# GD32F207RG.net
KiCad netlist of a schematic drawn in EAGLE
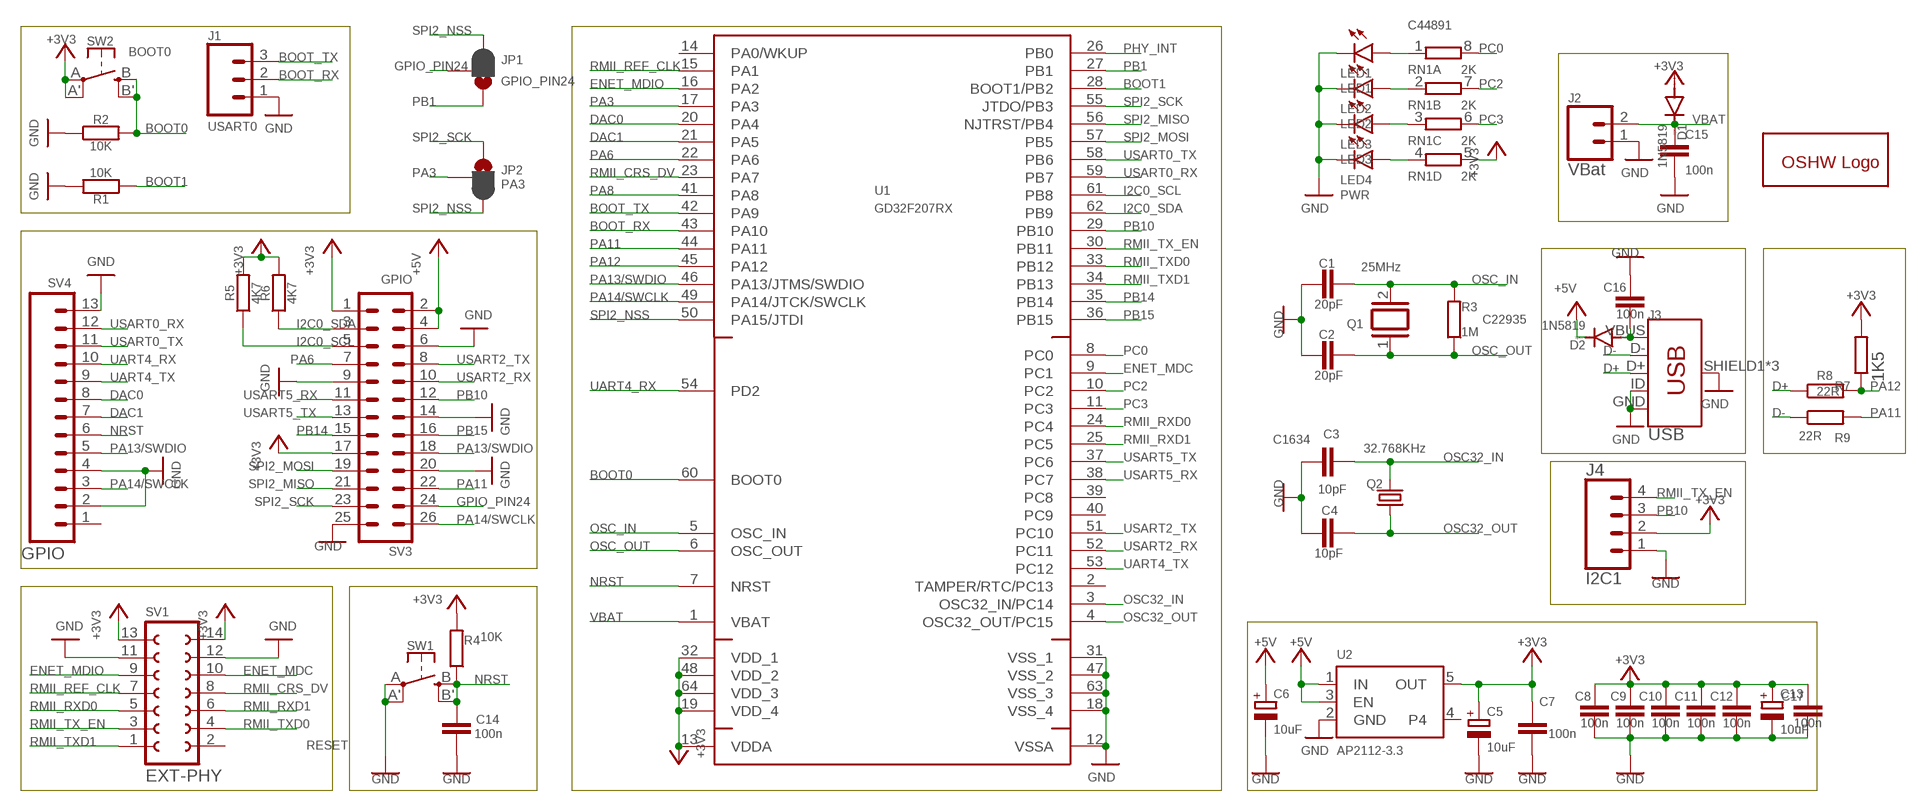
[diagram p0: schematic, sheet 1]

(export (version "E")
  (design (tool "Eeschema 10.0.6"))
  (components
    (comp (ref "C1")
      (value "20pF")
      (footprint "eagle-import:C0603")
      (libsource (lib "eagle-import") (part "C-EUC0603"))
    )
    (comp (ref "C2")
      (value "20pF")
      (footprint "eagle-import:C0603")
      (libsource (lib "eagle-import") (part "C-EUC0603"))
    )
    (comp (ref "C3")
      (value "10pF")
      (footprint "eagle-import:C0603")
      (fields (field (name "JLCPCB") "C1634"))
      (libsource (lib "eagle-import") (part "C-EUC0603"))
    )
    (comp (ref "C4")
      (value "10pF")
      (footprint "eagle-import:C0603")
      (libsource (lib "eagle-import") (part "C-EUC0603"))
    )
    (comp (ref "C5")
      (value "10uF")
      (footprint "eagle-import:A_3216-18R")
      (libsource (lib "eagle-import") (part "CPOL-EUA/3216-18R"))
    )
    (comp (ref "C6")
      (value "10uF")
      (footprint "eagle-import:A_3216-18R")
      (libsource (lib "eagle-import") (part "CPOL-EUA/3216-18R"))
    )
    (comp (ref "C7")
      (value "100n")
      (footprint "eagle-import:C0603")
      (libsource (lib "eagle-import") (part "C-EUC0603"))
    )
    (comp (ref "C8")
      (value "100n")
      (footprint "eagle-import:C0603")
      (libsource (lib "eagle-import") (part "C-EUC0603"))
    )
    (comp (ref "C9")
      (value "100n")
      (footprint "eagle-import:C0603")
      (libsource (lib "eagle-import") (part "C-EUC0603"))
    )
    (comp (ref "C10")
      (value "100n")
      (footprint "eagle-import:C0603")
      (libsource (lib "eagle-import") (part "C-EUC0603"))
    )
    (comp (ref "C11")
      (value "100n")
      (footprint "eagle-import:C0603")
      (libsource (lib "eagle-import") (part "C-EUC0603"))
    )
    (comp (ref "C12")
      (value "100n")
      (footprint "eagle-import:C0603")
      (libsource (lib "eagle-import") (part "C-EUC0603"))
    )
    (comp (ref "C13")
      (value "10uF")
      (footprint "eagle-import:A_3216-18R")
      (libsource (lib "eagle-import") (part "CPOL-EUA/3216-18R"))
    )
    (comp (ref "C14")
      (value "100n")
      (footprint "eagle-import:C0603")
      (libsource (lib "eagle-import") (part "C-EUC0603"))
    )
    (comp (ref "C15")
      (value "100n")
      (footprint "eagle-import:C0603")
      (libsource (lib "eagle-import") (part "C-EUC0603"))
    )
    (comp (ref "C16")
      (value "100n")
      (footprint "eagle-import:C0603")
      (libsource (lib "eagle-import") (part "C-EUC0603"))
    )
    (comp (ref "C17")
      (value "100n")
      (footprint "eagle-import:C0603")
      (libsource (lib "eagle-import") (part "C-EUC0603"))
    )
    (comp (ref "D1")
      (value "1N5819")
      (footprint "eagle-import:SOD323-R")
      (libsource (lib "eagle-import") (part "DIODE-SOD323-R"))
    )
    (comp (ref "D2")
      (value "1N5819")
      (footprint "eagle-import:SOD323-R")
      (libsource (lib "eagle-import") (part "DIODE-SOD323-R"))
    )
    (comp (ref "GOLD_ORB_SM1")
      (value "OSHWLOGOLOGO5MM")
      (footprint "eagle-import:OSHW_5MM")
      (libsource (lib "eagle-import") (part "OSHWLOGOLOGO5MM"))
    )
    (comp (ref "J1")
      (value "USART0")
      (footprint "eagle-import:1X03")
      (libsource (lib "eagle-import") (part "CONN_03"))
    )
    (comp (ref "J2")
      (value "VBat")
      (footprint "eagle-import:JST-2-PTH")
      (libsource (lib "eagle-import") (part "CONN_02JST-PTH-2"))
    )
    (comp (ref "J3")
      (value "USB")
      (footprint "eagle-import:USB-B-MICRO-SMD")
      (libsource (lib "eagle-import") (part "USB_MICRO-B_FEMALE-SMT"))
    )
    (comp (ref "J4")
      (value "I2C1")
      (footprint "eagle-import:1X04")
      (libsource (lib "eagle-import") (part "CONN_04"))
    )
    (comp (ref "JP1")
      (value "GPIO_PIN24")
      (footprint "eagle-import:SMT-JUMPER_3_1-NC_PASTE_SILK")
      (libsource (lib "eagle-import") (part "JUMPER-SMT_3_1-NC_PASTE_SILK"))
    )
    (comp (ref "JP2")
      (value "PA3")
      (footprint "eagle-import:SMT-JUMPER_3_1-NC_PASTE_SILK")
      (libsource (lib "eagle-import") (part "JUMPER-SMT_3_1-NC_PASTE_SILK"))
    )
    (comp (ref "LED1")
      (value "LED1")
      (footprint "eagle-import:CHIP-LED0603")
      (libsource (lib "eagle-import") (part "LEDCHIP-LED0603"))
    )
    (comp (ref "LED2")
      (value "LED2")
      (footprint "eagle-import:CHIP-LED0603")
      (libsource (lib "eagle-import") (part "LEDCHIP-LED0603"))
    )
    (comp (ref "LED3")
      (value "LED3")
      (footprint "eagle-import:CHIP-LED0603")
      (libsource (lib "eagle-import") (part "LEDCHIP-LED0603"))
    )
    (comp (ref "LED4")
      (value "PWR")
      (footprint "eagle-import:CHIP-LED0603")
      (libsource (lib "eagle-import") (part "LEDCHIP-LED0603"))
    )
    (comp (ref "Q1")
      (value "25MHz")
      (footprint "eagle-import:QS")
      (libsource (lib "eagle-import") (part "XTAL/S"))
    )
    (comp (ref "Q2")
      (value "32.768KHz")
      (footprint "eagle-import:TC26H")
      (libsource (lib "eagle-import") (part "CRYSTALTC26H"))
    )
    (comp (ref "R1")
      (value "10K")
      (footprint "eagle-import:R0603")
      (libsource (lib "eagle-import") (part "R-EU_R0603"))
    )
    (comp (ref "R2")
      (value "10K")
      (footprint "eagle-import:R0603")
      (libsource (lib "eagle-import") (part "R-EU_R0603"))
    )
    (comp (ref "R3")
      (value "1M")
      (footprint "eagle-import:R0603")
      (fields (field (name "JLCPCB") "C22935"))
      (libsource (lib "eagle-import") (part "R-EU_R0603"))
    )
    (comp (ref "R4")
      (value "10K")
      (footprint "eagle-import:R0603")
      (libsource (lib "eagle-import") (part "R-EU_R0603"))
    )
    (comp (ref "R5")
      (value "4K7")
      (footprint "eagle-import:R0603")
      (libsource (lib "eagle-import") (part "R-EU_R0603"))
    )
    (comp (ref "R6")
      (value "4K7")
      (footprint "eagle-import:R0603")
      (libsource (lib "eagle-import") (part "R-EU_R0603"))
    )
    (comp (ref "R7")
      (value "1K5")
      (footprint "eagle-import:R0603")
      (libsource (lib "eagle-import") (part "R-EU_R0603"))
    )
    (comp (ref "R8")
      (value "22R")
      (footprint "eagle-import:R0603")
      (libsource (lib "eagle-import") (part "R-EU_R0603"))
    )
    (comp (ref "R9")
      (value "22R")
      (footprint "eagle-import:R0603")
      (libsource (lib "eagle-import") (part "R-EU_R0603"))
    )
    (comp (ref "RN1")
      (value "2K")
      (footprint "eagle-import:4X0402ARV341")
      (fields (field (name "JLCPCB") "C44891"))
      (libsource (lib "eagle-import") (part "4R-N0402ARV341"))
    )
    (comp (ref "SV1")
      (value "EXT-PHY")
      (footprint "eagle-import:FE07-2W")
      (libsource (lib "eagle-import") (part "FE07-2W"))
    )
    (comp (ref "SV3")
      (value "GPIO")
      (footprint "eagle-import:MA13-2")
      (libsource (lib "eagle-import") (part "MA13-2"))
    )
    (comp (ref "SV4")
      (value "GPIO")
      (footprint "eagle-import:1X13")
      (libsource (lib "eagle-import") (part "CONN_13"))
    )
    (comp (ref "SW1")
      (value "RESET")
      (footprint "eagle-import:EVQ-Q2")
      (libsource (lib "eagle-import") (part "SPST_TACT-EVQQ2"))
    )
    (comp (ref "SW2")
      (value "BOOT0")
      (footprint "eagle-import:EVQ-Q2")
      (libsource (lib "eagle-import") (part "SPST_TACT-EVQQ2"))
    )
    (comp (ref "U1")
      (value "GD32F207RX")
      (footprint "eagle-import:LQFP64")
      (libsource (lib "eagle-import") (part "GD32F207RX"))
    )
    (comp (ref "U2")
      (value "AP2112-3.3")
      (footprint "eagle-import:SOT23-5")
      (libsource (lib "eagle-import") (part "VREG_SOT23-5"))
    )
  )
  (nets
    (net (code "1") (name "+3V3") (class "Default")
      (node (ref "C10") (pin "1") (pinfunction "1_1") (pintype "passive"))
      (node (ref "C11") (pin "1") (pinfunction "1_1") (pintype "passive"))
      (node (ref "C12") (pin "1") (pinfunction "1_1") (pintype "passive"))
      (node (ref "C13") (pin "+") (pinfunction "+_+") (pintype "passive"))
      (node (ref "C17") (pin "1") (pinfunction "1_1") (pintype "passive"))
      (node (ref "C5") (pin "+") (pinfunction "+_+") (pintype "passive"))
      (node (ref "C7") (pin "1") (pinfunction "1_1") (pintype "passive"))
      (node (ref "C8") (pin "1") (pinfunction "1_1") (pintype "passive"))
      (node (ref "C9") (pin "1") (pinfunction "1_1") (pintype "passive"))
      (node (ref "D1") (pin "A") (pinfunction "A_A") (pintype "passive"))
      (node (ref "J4") (pin "2") (pinfunction "2_2") (pintype "passive"))
      (node (ref "R4") (pin "2") (pinfunction "2_2") (pintype "passive"))
      (node (ref "R5") (pin "2") (pinfunction "2_2") (pintype "passive"))
      (node (ref "R6") (pin "2") (pinfunction "2_2") (pintype "passive"))
      (node (ref "R7") (pin "2") (pinfunction "2_2") (pintype "passive"))
      (node (ref "RN1") (pin "5") (pinfunction "2_5") (pintype "passive"))
      (node (ref "SV1") (pin "13") (pinfunction "13_13") (pintype "passive"))
      (node (ref "SV1") (pin "14") (pinfunction "14_14") (pintype "passive"))
      (node (ref "SV3") (pin "1") (pinfunction "1_1") (pintype "passive"))
      (node (ref "SV3") (pin "17") (pinfunction "17_17") (pintype "passive"))
      (node (ref "SW2") (pin "A") (pinfunction "P_A") (pintype "passive"))
      (node (ref "SW2") (pin "A'") (pinfunction "P1_A'") (pintype "passive"))
      (node (ref "U1") (pin "13") (pinfunction "VDDA_13") (pintype "power_in"))
      (node (ref "U1") (pin "19") (pinfunction "VDD_4_19") (pintype "power_in"))
      (node (ref "U1") (pin "32") (pinfunction "VDD_1_32") (pintype "power_in"))
      (node (ref "U1") (pin "48") (pinfunction "VDD_2_48") (pintype "power_in"))
      (node (ref "U1") (pin "64") (pinfunction "VDD_3_64") (pintype "power_in"))
      (node (ref "U2") (pin "5") (pinfunction "OUT_5") (pintype "power_in"))
    )
    (net (code "2") (name "+5V") (class "Default")
      (node (ref "C6") (pin "+") (pinfunction "+_+") (pintype "passive"))
      (node (ref "D2") (pin "C") (pinfunction "C_C") (pintype "passive"))
      (node (ref "SV3") (pin "2") (pinfunction "2_2") (pintype "passive"))
      (node (ref "SV3") (pin "4") (pinfunction "4_4") (pintype "passive"))
      (node (ref "U2") (pin "1") (pinfunction "IN_1") (pintype "power_in"))
      (node (ref "U2") (pin "3") (pinfunction "EN_3") (pintype "input"))
    )
    (net (code "3") (name "/BOOT0") (class "Default")
      (node (ref "R2") (pin "2") (pinfunction "2_2") (pintype "passive"))
      (node (ref "SW2") (pin "B") (pinfunction "S_B") (pintype "passive"))
      (node (ref "SW2") (pin "B'") (pinfunction "S1_B'") (pintype "passive"))
      (node (ref "U1") (pin "60") (pinfunction "BOOT0_60") (pintype "bidirectional"))
    )
    (net (code "4") (name "/BOOT1") (class "Default")
      (node (ref "R1") (pin "1") (pinfunction "1_1") (pintype "passive"))
      (node (ref "U1") (pin "28") (pinfunction "BOOT1/PB2_28") (pintype "bidirectional"))
    )
    (net (code "5") (name "/BOOT_RX") (class "Default")
      (node (ref "J1") (pin "2") (pinfunction "2_2") (pintype "passive"))
      (node (ref "U1") (pin "43") (pinfunction "PA10_43") (pintype "bidirectional"))
    )
    (net (code "6") (name "/BOOT_TX") (class "Default")
      (node (ref "J1") (pin "3") (pinfunction "3_3") (pintype "passive"))
      (node (ref "U1") (pin "42") (pinfunction "PA9_42") (pintype "bidirectional"))
    )
    (net (code "7") (name "/D+") (class "Default")
      (node (ref "J3") (pin "D+") (pinfunction "D+_D+") (pintype "bidirectional"))
      (node (ref "R8") (pin "1") (pinfunction "1_1") (pintype "passive"))
    )
    (net (code "8") (name "/D-") (class "Default")
      (node (ref "J3") (pin "D-") (pinfunction "D-_D-") (pintype "bidirectional"))
      (node (ref "R9") (pin "1") (pinfunction "1_1") (pintype "passive"))
    )
    (net (code "9") (name "/DAC0") (class "Default")
      (node (ref "SV4") (pin "8") (pinfunction "8_8") (pintype "passive"))
      (node (ref "U1") (pin "20") (pinfunction "PA4_20") (pintype "bidirectional"))
    )
    (net (code "10") (name "/DAC1") (class "Default")
      (node (ref "SV4") (pin "7") (pinfunction "7_7") (pintype "passive"))
      (node (ref "U1") (pin "21") (pinfunction "PA5_21") (pintype "bidirectional"))
    )
    (net (code "11") (name "/ENET_MDC") (class "Default")
      (node (ref "SV1") (pin "10") (pinfunction "10_10") (pintype "passive"))
      (node (ref "U1") (pin "9") (pinfunction "PC1_9") (pintype "bidirectional"))
    )
    (net (code "12") (name "/ENET_MDIO") (class "Default")
      (node (ref "SV1") (pin "9") (pinfunction "9_9") (pintype "passive"))
      (node (ref "U1") (pin "16") (pinfunction "PA2_16") (pintype "bidirectional"))
    )
    (net (code "13") (name "/GPIO_PIN24") (class "Default")
      (node (ref "JP1") (pin "2") (pinfunction "2_2") (pintype "passive"))
      (node (ref "SV3") (pin "24") (pinfunction "24_24") (pintype "passive"))
    )
    (net (code "14") (name "/I2C0_SCL") (class "Default")
      (node (ref "R5") (pin "1") (pinfunction "1_1") (pintype "passive"))
      (node (ref "SV3") (pin "5") (pinfunction "5_5") (pintype "passive"))
      (node (ref "U1") (pin "61") (pinfunction "PB8_61") (pintype "bidirectional"))
    )
    (net (code "15") (name "/I2C0_SDA") (class "Default")
      (node (ref "R6") (pin "1") (pinfunction "1_1") (pintype "passive"))
      (node (ref "SV3") (pin "3") (pinfunction "3_3") (pintype "passive"))
      (node (ref "U1") (pin "62") (pinfunction "PB9_62") (pintype "bidirectional"))
    )
    (net (code "16") (name "/NRST") (class "Default")
      (node (ref "C14") (pin "1") (pinfunction "1_1") (pintype "passive"))
      (node (ref "R4") (pin "1") (pinfunction "1_1") (pintype "passive"))
      (node (ref "SV4") (pin "6") (pinfunction "6_6") (pintype "passive"))
      (node (ref "SW1") (pin "B") (pinfunction "S_B") (pintype "passive"))
      (node (ref "SW1") (pin "B'") (pinfunction "S1_B'") (pintype "passive"))
      (node (ref "U1") (pin "7") (pinfunction "NRST_7") (pintype "power_in"))
    )
    (net (code "17") (name "/OSC32_IN") (class "Default")
      (node (ref "C3") (pin "2") (pinfunction "2_2") (pintype "passive"))
      (node (ref "Q2") (pin "2") (pinfunction "2_2") (pintype "passive"))
      (node (ref "U1") (pin "3") (pinfunction "OSC32_IN/PC14_3") (pintype "bidirectional"))
    )
    (net (code "18") (name "/OSC32_OUT") (class "Default")
      (node (ref "C4") (pin "2") (pinfunction "2_2") (pintype "passive"))
      (node (ref "Q2") (pin "1") (pinfunction "1_1") (pintype "passive"))
      (node (ref "U1") (pin "4") (pinfunction "OSC32_OUT/PC15_4") (pintype "bidirectional"))
    )
    (net (code "19") (name "/OSC_IN") (class "Default")
      (node (ref "C1") (pin "2") (pinfunction "2_2") (pintype "passive"))
      (node (ref "Q1") (pin "2") (pinfunction "2_2") (pintype "passive"))
      (node (ref "R3") (pin "2") (pinfunction "2_2") (pintype "passive"))
      (node (ref "U1") (pin "5") (pinfunction "OSC_IN_5") (pintype "bidirectional"))
    )
    (net (code "20") (name "/OSC_OUT") (class "Default")
      (node (ref "C2") (pin "2") (pinfunction "2_2") (pintype "passive"))
      (node (ref "Q1") (pin "1") (pinfunction "1_1") (pintype "passive"))
      (node (ref "R3") (pin "1") (pinfunction "1_1") (pintype "passive"))
      (node (ref "U1") (pin "6") (pinfunction "OSC_OUT_6") (pintype "bidirectional"))
    )
    (net (code "21") (name "/PA3") (class "Default")
      (node (ref "JP2") (pin "2") (pinfunction "2_2") (pintype "passive"))
      (node (ref "U1") (pin "17") (pinfunction "PA3_17") (pintype "bidirectional"))
    )
    (net (code "22") (name "/PA6") (class "Default")
      (node (ref "SV3") (pin "7") (pinfunction "7_7") (pintype "passive"))
      (node (ref "U1") (pin "22") (pinfunction "PA6_22") (pintype "bidirectional"))
    )
    (net (code "23") (name "/PA8") (class "Default")
      (node (ref "U1") (pin "41") (pinfunction "PA8_41") (pintype "bidirectional"))
    )
    (net (code "24") (name "/PA11") (class "Default")
      (node (ref "R9") (pin "2") (pinfunction "2_2") (pintype "passive"))
      (node (ref "SV3") (pin "22") (pinfunction "22_22") (pintype "passive"))
      (node (ref "U1") (pin "44") (pinfunction "PA11_44") (pintype "bidirectional"))
    )
    (net (code "25") (name "/PA12") (class "Default")
      (node (ref "R7") (pin "1") (pinfunction "1_1") (pintype "passive"))
      (node (ref "R8") (pin "2") (pinfunction "2_2") (pintype "passive"))
      (node (ref "U1") (pin "45") (pinfunction "PA12_45") (pintype "bidirectional"))
    )
    (net (code "26") (name "/PA13{slash}SWDIO") (class "Default")
      (node (ref "SV3") (pin "18") (pinfunction "18_18") (pintype "passive"))
      (node (ref "SV4") (pin "5") (pinfunction "5_5") (pintype "passive"))
      (node (ref "U1") (pin "46") (pinfunction "PA13/JTMS/SWDIO_46") (pintype "bidirectional"))
    )
    (net (code "27") (name "/PA14{slash}SWCLK") (class "Default")
      (node (ref "SV3") (pin "26") (pinfunction "26_26") (pintype "passive"))
      (node (ref "SV4") (pin "3") (pinfunction "3_3") (pintype "passive"))
      (node (ref "U1") (pin "49") (pinfunction "PA14/JTCK/SWCLK_49") (pintype "bidirectional"))
    )
    (net (code "28") (name "/PB1") (class "Default")
      (node (ref "JP1") (pin "1") (pinfunction "1_1") (pintype "passive"))
      (node (ref "U1") (pin "27") (pinfunction "PB1_27") (pintype "bidirectional"))
    )
    (net (code "29") (name "/PB10") (class "Default")
      (node (ref "J4") (pin "3") (pinfunction "3_3") (pintype "passive"))
      (node (ref "SV3") (pin "12") (pinfunction "12_12") (pintype "passive"))
      (node (ref "U1") (pin "29") (pinfunction "PB10_29") (pintype "bidirectional"))
    )
    (net (code "30") (name "/PB14") (class "Default")
      (node (ref "SV3") (pin "15") (pinfunction "15_15") (pintype "passive"))
      (node (ref "U1") (pin "35") (pinfunction "PB14_35") (pintype "bidirectional"))
    )
    (net (code "31") (name "/PB15") (class "Default")
      (node (ref "SV3") (pin "16") (pinfunction "16_16") (pintype "passive"))
      (node (ref "U1") (pin "36") (pinfunction "PB15_36") (pintype "bidirectional"))
    )
    (net (code "32") (name "/PC0") (class "Default")
      (node (ref "RN1") (pin "8") (pinfunction "2_8") (pintype "passive"))
      (node (ref "U1") (pin "8") (pinfunction "PC0_8") (pintype "bidirectional"))
    )
    (net (code "33") (name "/PC2") (class "Default")
      (node (ref "RN1") (pin "7") (pinfunction "2_7") (pintype "passive"))
      (node (ref "U1") (pin "10") (pinfunction "PC2_10") (pintype "bidirectional"))
    )
    (net (code "34") (name "/PC3") (class "Default")
      (node (ref "RN1") (pin "6") (pinfunction "2_6") (pintype "passive"))
      (node (ref "U1") (pin "11") (pinfunction "PC3_11") (pintype "bidirectional"))
    )
    (net (code "35") (name "/PHY_INT") (class "Default")
      (node (ref "U1") (pin "26") (pinfunction "PB0_26") (pintype "bidirectional"))
    )
    (net (code "36") (name "/RMII_CRS_DV") (class "Default")
      (node (ref "SV1") (pin "8") (pinfunction "8_8") (pintype "passive"))
      (node (ref "U1") (pin "23") (pinfunction "PA7_23") (pintype "bidirectional"))
    )
    (net (code "37") (name "/RMII_REF_CLK") (class "Default")
      (node (ref "SV1") (pin "7") (pinfunction "7_7") (pintype "passive"))
      (node (ref "U1") (pin "15") (pinfunction "PA1_15") (pintype "bidirectional"))
    )
    (net (code "38") (name "/RMII_RXD0") (class "Default")
      (node (ref "SV1") (pin "5") (pinfunction "5_5") (pintype "passive"))
      (node (ref "U1") (pin "24") (pinfunction "PC4_24") (pintype "bidirectional"))
    )
    (net (code "39") (name "/RMII_RXD1") (class "Default")
      (node (ref "SV1") (pin "6") (pinfunction "6_6") (pintype "passive"))
      (node (ref "U1") (pin "25") (pinfunction "PC5_25") (pintype "bidirectional"))
    )
    (net (code "40") (name "/RMII_TXD0") (class "Default")
      (node (ref "SV1") (pin "4") (pinfunction "4_4") (pintype "passive"))
      (node (ref "U1") (pin "33") (pinfunction "PB12_33") (pintype "bidirectional"))
    )
    (net (code "41") (name "/RMII_TXD1") (class "Default")
      (node (ref "SV1") (pin "1") (pinfunction "1_1") (pintype "passive"))
      (node (ref "U1") (pin "34") (pinfunction "PB13_34") (pintype "bidirectional"))
    )
    (net (code "42") (name "/RMII_TX_EN") (class "Default")
      (node (ref "J4") (pin "4") (pinfunction "4_4") (pintype "passive"))
      (node (ref "SV1") (pin "3") (pinfunction "3_3") (pintype "passive"))
      (node (ref "U1") (pin "30") (pinfunction "PB11_30") (pintype "bidirectional"))
    )
    (net (code "43") (name "/SPI2_MISO") (class "Default")
      (node (ref "SV3") (pin "21") (pinfunction "21_21") (pintype "passive"))
      (node (ref "U1") (pin "56") (pinfunction "NJTRST/PB4_56") (pintype "bidirectional"))
    )
    (net (code "44") (name "/SPI2_MOSI") (class "Default")
      (node (ref "SV3") (pin "19") (pinfunction "19_19") (pintype "passive"))
      (node (ref "U1") (pin "57") (pinfunction "PB5_57") (pintype "bidirectional"))
    )
    (net (code "45") (name "/SPI2_NSS") (class "Default")
      (node (ref "JP1") (pin "3") (pinfunction "3_3") (pintype "passive"))
      (node (ref "JP2") (pin "3") (pinfunction "3_3") (pintype "passive"))
      (node (ref "U1") (pin "50") (pinfunction "PA15/JTDI_50") (pintype "bidirectional"))
    )
    (net (code "46") (name "/SPI2_SCK") (class "Default")
      (node (ref "JP2") (pin "1") (pinfunction "1_1") (pintype "passive"))
      (node (ref "SV3") (pin "23") (pinfunction "23_23") (pintype "passive"))
      (node (ref "U1") (pin "55") (pinfunction "JTDO/PB3_55") (pintype "bidirectional"))
    )
    (net (code "47") (name "/UART4_RX") (class "Default")
      (node (ref "SV4") (pin "10") (pinfunction "10_10") (pintype "passive"))
      (node (ref "U1") (pin "54") (pinfunction "PD2_54") (pintype "bidirectional"))
    )
    (net (code "48") (name "/UART4_TX") (class "Default")
      (node (ref "SV4") (pin "9") (pinfunction "9_9") (pintype "passive"))
      (node (ref "U1") (pin "53") (pinfunction "PC12_53") (pintype "bidirectional"))
    )
    (net (code "49") (name "/USART0_RX") (class "Default")
      (node (ref "SV4") (pin "12") (pinfunction "12_12") (pintype "passive"))
      (node (ref "U1") (pin "59") (pinfunction "PB7_59") (pintype "bidirectional"))
    )
    (net (code "50") (name "/USART0_TX") (class "Default")
      (node (ref "SV4") (pin "11") (pinfunction "11_11") (pintype "passive"))
      (node (ref "U1") (pin "58") (pinfunction "PB6_58") (pintype "bidirectional"))
    )
    (net (code "51") (name "/USART2_RX") (class "Default")
      (node (ref "SV3") (pin "10") (pinfunction "10_10") (pintype "passive"))
      (node (ref "U1") (pin "52") (pinfunction "PC11_52") (pintype "bidirectional"))
    )
    (net (code "52") (name "/USART2_TX") (class "Default")
      (node (ref "SV3") (pin "8") (pinfunction "8_8") (pintype "passive"))
      (node (ref "U1") (pin "51") (pinfunction "PC10_51") (pintype "bidirectional"))
    )
    (net (code "53") (name "/USART5_RX") (class "Default")
      (node (ref "SV3") (pin "11") (pinfunction "11_11") (pintype "passive"))
      (node (ref "U1") (pin "38") (pinfunction "PC7_38") (pintype "bidirectional"))
    )
    (net (code "54") (name "/USART5_TX") (class "Default")
      (node (ref "SV3") (pin "13") (pinfunction "13_13") (pintype "passive"))
      (node (ref "U1") (pin "37") (pinfunction "PC6_37") (pintype "bidirectional"))
    )
    (net (code "55") (name "/VBAT") (class "Default")
      (node (ref "C15") (pin "1") (pinfunction "1_1") (pintype "passive"))
      (node (ref "D1") (pin "C") (pinfunction "C_C") (pintype "passive"))
      (node (ref "J2") (pin "2") (pinfunction "2_2") (pintype "passive"))
      (node (ref "U1") (pin "1") (pinfunction "VBAT_1") (pintype "power_in"))
    )
    (net (code "56") (name "GND") (class "Default")
      (node (ref "C1") (pin "1") (pinfunction "1_1") (pintype "passive"))
      (node (ref "C10") (pin "2") (pinfunction "2_2") (pintype "passive"))
      (node (ref "C11") (pin "2") (pinfunction "2_2") (pintype "passive"))
      (node (ref "C12") (pin "2") (pinfunction "2_2") (pintype "passive"))
      (node (ref "C13") (pin "-") (pinfunction "-_-") (pintype "passive"))
      (node (ref "C14") (pin "2") (pinfunction "2_2") (pintype "passive"))
      (node (ref "C15") (pin "2") (pinfunction "2_2") (pintype "passive"))
      (node (ref "C16") (pin "1") (pinfunction "1_1") (pintype "passive"))
      (node (ref "C17") (pin "2") (pinfunction "2_2") (pintype "passive"))
      (node (ref "C2") (pin "1") (pinfunction "1_1") (pintype "passive"))
      (node (ref "C3") (pin "1") (pinfunction "1_1") (pintype "passive"))
      (node (ref "C4") (pin "1") (pinfunction "1_1") (pintype "passive"))
      (node (ref "C5") (pin "-") (pinfunction "-_-") (pintype "passive"))
      (node (ref "C6") (pin "-") (pinfunction "-_-") (pintype "passive"))
      (node (ref "C7") (pin "2") (pinfunction "2_2") (pintype "passive"))
      (node (ref "C8") (pin "2") (pinfunction "2_2") (pintype "passive"))
      (node (ref "C9") (pin "2") (pinfunction "2_2") (pintype "passive"))
      (node (ref "J1") (pin "1") (pinfunction "1_1") (pintype "passive"))
      (node (ref "J2") (pin "1") (pinfunction "1_1") (pintype "passive"))
      (node (ref "J3") (pin "GND") (pinfunction "GND_GND") (pintype "power_in"))
      (node (ref "J3") (pin "ID") (pinfunction "ID_ID") (pintype "bidirectional"))
      (node (ref "J3") (pin "SHIELD1") (pinfunction "SHIELD_SHIELD1") (pintype "bidirectional"))
      (node (ref "J3") (pin "SHIELD2") (pinfunction "SHIELD_SHIELD2") (pintype "bidirectional"))
      (node (ref "J3") (pin "SHIELD3") (pinfunction "SHIELD_SHIELD3") (pintype "bidirectional"))
      (node (ref "J4") (pin "1") (pinfunction "1_1") (pintype "passive"))
      (node (ref "LED1") (pin "C") (pinfunction "C_C") (pintype "passive"))
      (node (ref "LED2") (pin "C") (pinfunction "C_C") (pintype "passive"))
      (node (ref "LED3") (pin "C") (pinfunction "C_C") (pintype "passive"))
      (node (ref "LED4") (pin "C") (pinfunction "C_C") (pintype "passive"))
      (node (ref "R1") (pin "2") (pinfunction "2_2") (pintype "passive"))
      (node (ref "R2") (pin "1") (pinfunction "1_1") (pintype "passive"))
      (node (ref "SV1") (pin "11") (pinfunction "11_11") (pintype "passive"))
      (node (ref "SV1") (pin "12") (pinfunction "12_12") (pintype "passive"))
      (node (ref "SV3") (pin "14") (pinfunction "14_14") (pintype "passive"))
      (node (ref "SV3") (pin "20") (pinfunction "20_20") (pintype "passive"))
      (node (ref "SV3") (pin "25") (pinfunction "25_25") (pintype "passive"))
      (node (ref "SV3") (pin "6") (pinfunction "6_6") (pintype "passive"))
      (node (ref "SV3") (pin "9") (pinfunction "9_9") (pintype "passive"))
      (node (ref "SV4") (pin "13") (pinfunction "13_13") (pintype "passive"))
      (node (ref "SV4") (pin "2") (pinfunction "2_2") (pintype "passive"))
      (node (ref "SV4") (pin "4") (pinfunction "4_4") (pintype "passive"))
      (node (ref "SW1") (pin "A") (pinfunction "P_A") (pintype "passive"))
      (node (ref "SW1") (pin "A'") (pinfunction "P1_A'") (pintype "passive"))
      (node (ref "U1") (pin "12") (pinfunction "VSSA_12") (pintype "power_in"))
      (node (ref "U1") (pin "18") (pinfunction "VSS_4_18") (pintype "power_in"))
      (node (ref "U1") (pin "31") (pinfunction "VSS_1_31") (pintype "power_in"))
      (node (ref "U1") (pin "47") (pinfunction "VSS_2_47") (pintype "power_in"))
      (node (ref "U1") (pin "63") (pinfunction "VSS_3_63") (pintype "power_in"))
      (node (ref "U2") (pin "2") (pinfunction "GND_2") (pintype "power_in"))
    )
    (net (code "57") (name "Net-(C16-Pad2)") (class "Default")
      (node (ref "C16") (pin "2") (pinfunction "2_2") (pintype "passive"))
      (node (ref "D2") (pin "A") (pinfunction "A_A") (pintype "passive"))
      (node (ref "J3") (pin "VBUS") (pinfunction "VBUS_VBUS") (pintype "power_in"))
    )
    (net (code "58") (name "Net-(LED1-PadA)") (class "Default")
      (node (ref "LED1") (pin "A") (pinfunction "A_A") (pintype "passive"))
      (node (ref "RN1") (pin "1") (pinfunction "1_1") (pintype "passive"))
    )
    (net (code "59") (name "Net-(RN1B-1)") (class "Default")
      (node (ref "LED2") (pin "A") (pinfunction "A_A") (pintype "passive"))
      (node (ref "RN1") (pin "2") (pinfunction "1_2") (pintype "passive"))
    )
    (net (code "60") (name "Net-(RN1C-1)") (class "Default")
      (node (ref "LED3") (pin "A") (pinfunction "A_A") (pintype "passive"))
      (node (ref "RN1") (pin "3") (pinfunction "1_3") (pintype "passive"))
    )
    (net (code "61") (name "Net-(RN1D-1)") (class "Default")
      (node (ref "LED4") (pin "A") (pinfunction "A_A") (pintype "passive"))
      (node (ref "RN1") (pin "4") (pinfunction "1_4") (pintype "passive"))
    )
    (net (code "62") (name "unconnected-(SV1-Pad2)") (class "Default")
      (node (ref "SV1") (pin "2") (pinfunction "2_2") (pintype "passive"))
    )
    (net (code "63") (name "unconnected-(SV4-Pad1)") (class "Default")
      (node (ref "SV4") (pin "1") (pinfunction "1_1") (pintype "passive"))
    )
    (net (code "64") (name "unconnected-(U1-PA0{slash}WKUP-Pad14)") (class "Default")
      (node (ref "U1") (pin "14") (pinfunction "PA0/WKUP_14") (pintype "bidirectional"))
    )
    (net (code "65") (name "unconnected-(U1-PC8-Pad39)") (class "Default")
      (node (ref "U1") (pin "39") (pinfunction "PC8_39") (pintype "bidirectional"))
    )
    (net (code "66") (name "unconnected-(U1-PC9-Pad40)") (class "Default")
      (node (ref "U1") (pin "40") (pinfunction "PC9_40") (pintype "bidirectional"))
    )
    (net (code "67") (name "unconnected-(U1-TAMPER{slash}RTC{slash}PC13-Pad2)") (class "Default")
      (node (ref "U1") (pin "2") (pinfunction "TAMPER/RTC/PC13_2") (pintype "bidirectional"))
    )
    (net (code "68") (name "unconnected-(U2-P4-Pad4)") (class "Default")
      (node (ref "U2") (pin "4") (pinfunction "P4_4") (pintype "bidirectional"))
    )
  )
)
